# DAC.net
KiCad netlist of a schematic drawn in Altium Designer
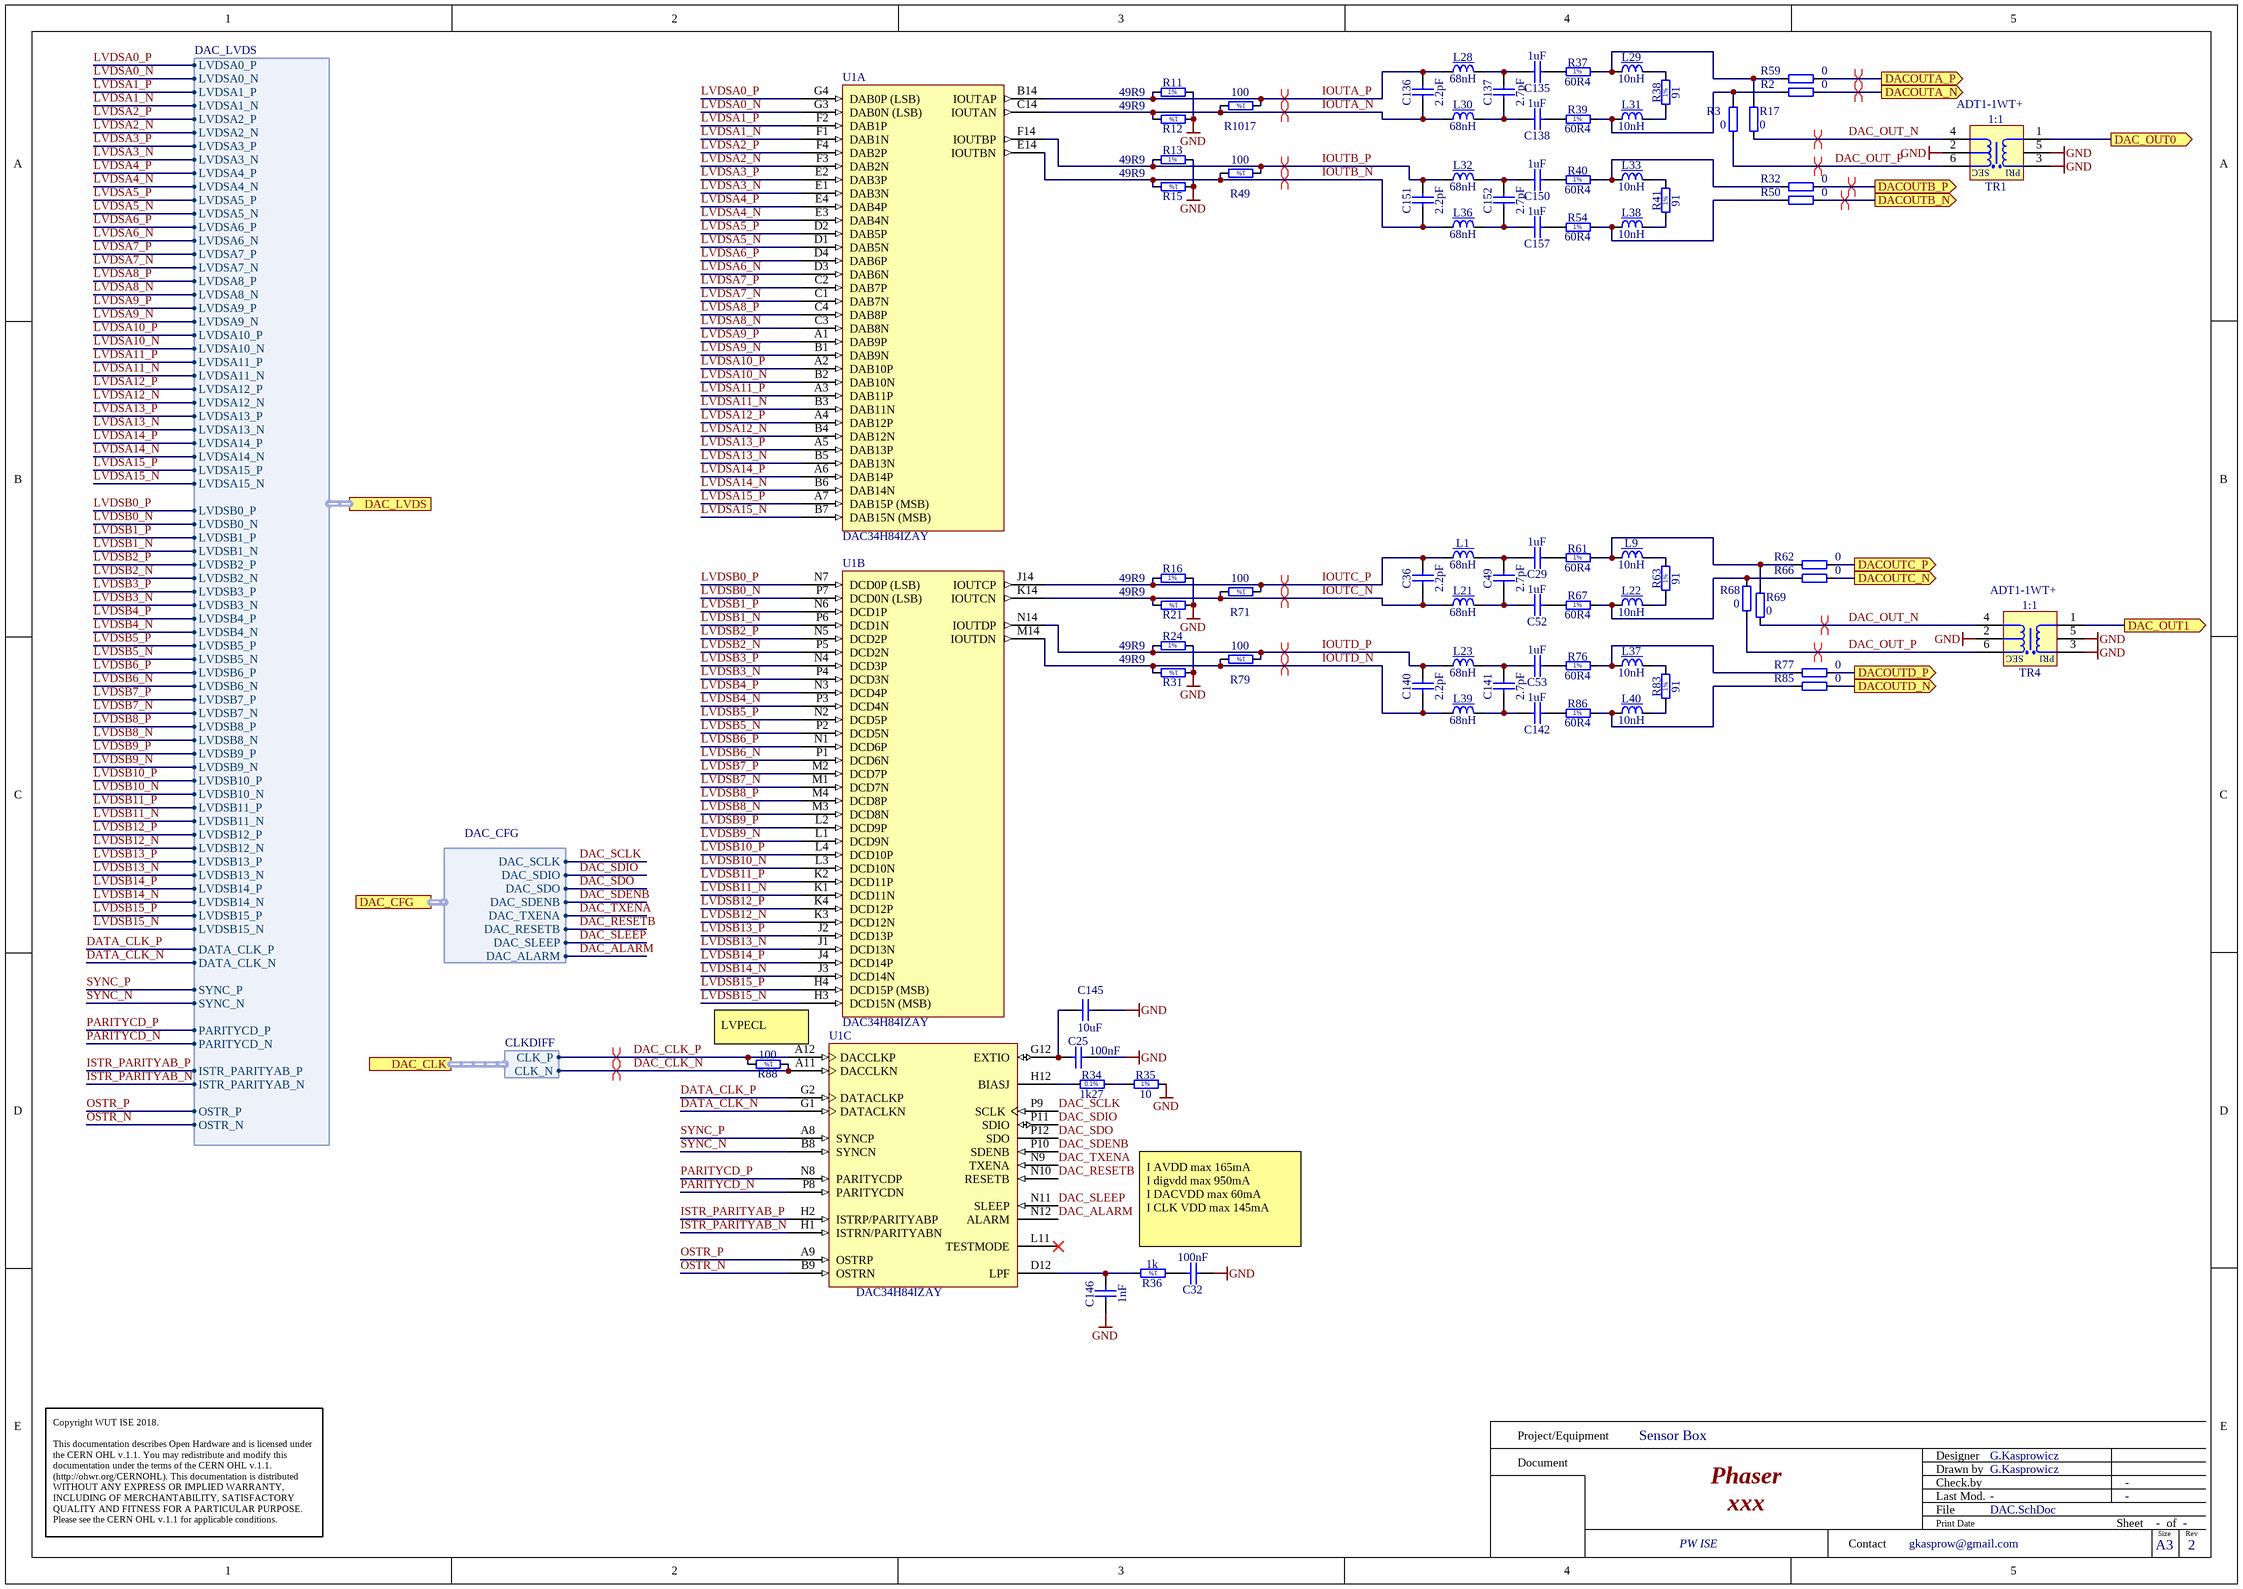
[diagram p0: DAC.SchDoc]

(export (version "E")
  (design (tool "Eeschema 10.0.6"))
  (components
    (comp (ref "C25")
      (value "100nF")
      (footprint "CAPC1005X55N")
      (description "Non-polarised capacitor")
      (fields (field (name "PART NUMBER") "CC0402_100NF_16V_10%_X5R") (field (name "VOLTAGE") "16V"))
      (libsource (lib "Capacitors") (part "Capacitor - non polarized"))
    )
    (comp (ref "C29")
      (value "1uF")
      (footprint "CAPC1005X55N")
      (description "Non-polarised capacitor")
      (fields (field (name "PART NUMBER") "CC0402_1UF_16V_10%_X5R") (field (name "VOLTAGE") "16V"))
      (libsource (lib "Capacitors") (part "Capacitor - non polarized"))
    )
    (comp (ref "C32")
      (value "100nF")
      (footprint "CAPC1608X90N")
      (description "Non-polarised capacitor")
      (fields (field (name "PART NUMBER") "CC0603_100NF_100V_10%_X7R") (field (name "VOLTAGE") "100V"))
      (libsource (lib "Capacitors") (part "Capacitor - non polarized"))
    )
    (comp (ref "C36")
      (value "2.2pF")
      (footprint "CAPC1608X87N")
      (description "Non-polarised capacitor")
      (fields (field (name "PART NUMBER") "CC0603_2.2PF_50V_0.25PF_NP0") (field (name "VOLTAGE") "50V"))
      (libsource (lib "Capacitors") (part "Capacitor - non polarized"))
    )
    (comp (ref "C49")
      (value "2.7pF")
      (footprint "CAPC1608X87N")
      (description "Non-polarised capacitor")
      (fields (field (name "PART NUMBER") "CC0603_2.7PF_50V_0.25PF_NP0") (field (name "VOLTAGE") "50V"))
      (libsource (lib "Capacitors") (part "Capacitor - non polarized"))
    )
    (comp (ref "C52")
      (value "1uF")
      (footprint "CAPC1005X55N")
      (description "Non-polarised capacitor")
      (fields (field (name "PART NUMBER") "CC0402_1UF_16V_10%_X5R") (field (name "VOLTAGE") "16V"))
      (libsource (lib "Capacitors") (part "Capacitor - non polarized"))
    )
    (comp (ref "C53")
      (value "1uF")
      (footprint "CAPC1005X55N")
      (description "Non-polarised capacitor")
      (fields (field (name "PART NUMBER") "CC0402_1UF_16V_10%_X5R") (field (name "VOLTAGE") "16V"))
      (libsource (lib "Capacitors") (part "Capacitor - non polarized"))
    )
    (comp (ref "C135")
      (value "1uF")
      (footprint "CAPC1005X55N")
      (description "Non-polarised capacitor")
      (fields (field (name "PART NUMBER") "CC0402_1UF_16V_10%_X5R") (field (name "VOLTAGE") "16V"))
      (libsource (lib "Capacitors") (part "Capacitor - non polarized"))
    )
    (comp (ref "C136")
      (value "2.2pF")
      (footprint "CAPC1608X87N")
      (description "Non-polarised capacitor")
      (fields (field (name "PART NUMBER") "CC0603_2.2PF_50V_0.25PF_NP0") (field (name "VOLTAGE") "50V"))
      (libsource (lib "Capacitors") (part "Capacitor - non polarized"))
    )
    (comp (ref "C137")
      (value "2.7pF")
      (footprint "CAPC1608X87N")
      (description "Non-polarised capacitor")
      (fields (field (name "PART NUMBER") "CC0603_2.7PF_50V_0.25PF_NP0") (field (name "VOLTAGE") "50V"))
      (libsource (lib "Capacitors") (part "Capacitor - non polarized"))
    )
    (comp (ref "C138")
      (value "1uF")
      (footprint "CAPC1005X55N")
      (description "Non-polarised capacitor")
      (fields (field (name "PART NUMBER") "CC0402_1UF_16V_10%_X5R") (field (name "VOLTAGE") "16V"))
      (libsource (lib "Capacitors") (part "Capacitor - non polarized"))
    )
    (comp (ref "C140")
      (value "2.2pF")
      (footprint "CAPC1608X87N")
      (description "Non-polarised capacitor")
      (fields (field (name "PART NUMBER") "CC0603_2.2PF_50V_0.25PF_NP0") (field (name "VOLTAGE") "50V"))
      (libsource (lib "Capacitors") (part "Capacitor - non polarized"))
    )
    (comp (ref "C141")
      (value "2.7pF")
      (footprint "CAPC1608X87N")
      (description "Non-polarised capacitor")
      (fields (field (name "PART NUMBER") "CC0603_2.7PF_50V_0.25PF_NP0") (field (name "VOLTAGE") "50V"))
      (libsource (lib "Capacitors") (part "Capacitor - non polarized"))
    )
    (comp (ref "C142")
      (value "1uF")
      (footprint "CAPC1005X55N")
      (description "Non-polarised capacitor")
      (fields (field (name "PART NUMBER") "CC0402_1UF_16V_10%_X5R") (field (name "VOLTAGE") "16V"))
      (libsource (lib "Capacitors") (part "Capacitor - non polarized"))
    )
    (comp (ref "C145")
      (value "10uF")
      (footprint "CAPC2012X95N")
      (description "Non-polarised capacitor")
      (fields (field (name "PART NUMBER") "CC0805_10UF_25V_10%_X5R") (field (name "VOLTAGE") "25V"))
      (libsource (lib "Capacitors") (part "Capacitor - non polarized"))
    )
    (comp (ref "C146")
      (value "1nF")
      (footprint "CAPC1608X90N")
      (description "Non-polarised capacitor")
      (fields (field (name "PART NUMBER") "CC0603_1NF_50V_1%_NP0") (field (name "VOLTAGE") "50V"))
      (libsource (lib "Capacitors") (part "Capacitor - non polarized"))
    )
    (comp (ref "C150")
      (value "1uF")
      (footprint "CAPC1005X55N")
      (description "Non-polarised capacitor")
      (fields (field (name "PART NUMBER") "CC0402_1UF_16V_10%_X5R") (field (name "VOLTAGE") "16V"))
      (libsource (lib "Capacitors") (part "Capacitor - non polarized"))
    )
    (comp (ref "C151")
      (value "2.2pF")
      (footprint "CAPC1608X87N")
      (description "Non-polarised capacitor")
      (fields (field (name "PART NUMBER") "CC0603_2.2PF_50V_0.25PF_NP0") (field (name "VOLTAGE") "50V"))
      (libsource (lib "Capacitors") (part "Capacitor - non polarized"))
    )
    (comp (ref "C152")
      (value "2.7pF")
      (footprint "CAPC1608X87N")
      (description "Non-polarised capacitor")
      (fields (field (name "PART NUMBER") "CC0603_2.7PF_50V_0.25PF_NP0") (field (name "VOLTAGE") "50V"))
      (libsource (lib "Capacitors") (part "Capacitor - non polarized"))
    )
    (comp (ref "C157")
      (value "1uF")
      (footprint "CAPC1005X55N")
      (description "Non-polarised capacitor")
      (fields (field (name "PART NUMBER") "CC0402_1UF_16V_10%_X5R") (field (name "VOLTAGE") "16V"))
      (libsource (lib "Capacitors") (part "Capacitor - non polarized"))
    )
    (comp (ref "L1")
      (value "68nH")
      (footprint "IND_COILCRAFT_0603HP")
      (description "Inductor With Core")
      (fields
        (field (name "PART NUMBER") "IND0603_68NH_2%_COILCRAFT_0603HP-68NXGLU")
        (field (name "POWER") "600mA")
      )
      (libsource (lib "Inductors & Transformers") (part "Inductor With Magnetic core"))
    )
    (comp (ref "L9")
      (value "10nH")
      (footprint "IND_COILCRAFT_0402DC")
      (description "Inductor With Core")
      (fields (field (name "PART NUMBER") "IND0402_10NH_2%_COILCRAFT_0402DC") (field (name "POWER") "1A"))
      (libsource (lib "Inductors_Transformers") (part "IND0402_10NH_2%_COILCRAFT_0402DC"))
    )
    (comp (ref "L21")
      (value "68nH")
      (footprint "IND_COILCRAFT_0603HP")
      (description "Inductor With Core")
      (fields
        (field (name "PART NUMBER") "IND0603_68NH_2%_COILCRAFT_0603HP-68NXGLU")
        (field (name "POWER") "600mA")
      )
      (libsource (lib "Inductors & Transformers") (part "Inductor With Magnetic core"))
    )
    (comp (ref "L22")
      (value "10nH")
      (footprint "IND_COILCRAFT_0402DC")
      (description "Inductor With Core")
      (fields (field (name "PART NUMBER") "IND0402_10NH_2%_COILCRAFT_0402DC") (field (name "POWER") "1A"))
      (libsource (lib "Inductors_Transformers") (part "IND0402_10NH_2%_COILCRAFT_0402DC"))
    )
    (comp (ref "L23")
      (value "68nH")
      (footprint "IND_COILCRAFT_0603HP")
      (description "Inductor With Core")
      (fields
        (field (name "PART NUMBER") "IND0603_68NH_2%_COILCRAFT_0603HP-68NXGLU")
        (field (name "POWER") "600mA")
      )
      (libsource (lib "Inductors & Transformers") (part "Inductor With Magnetic core"))
    )
    (comp (ref "L28")
      (value "68nH")
      (footprint "IND_COILCRAFT_0603HP")
      (description "Inductor With Core")
      (fields
        (field (name "PART NUMBER") "IND0603_68NH_2%_COILCRAFT_0603HP-68NXGLU")
        (field (name "POWER") "600mA")
      )
      (libsource (lib "Inductors & Transformers") (part "Inductor With Magnetic core"))
    )
    (comp (ref "L29")
      (value "10nH")
      (footprint "IND_COILCRAFT_0402DC")
      (description "Inductor With Core")
      (fields (field (name "PART NUMBER") "IND0402_10NH_2%_COILCRAFT_0402DC") (field (name "POWER") "1A"))
      (libsource (lib "Inductors_Transformers") (part "IND0402_10NH_2%_COILCRAFT_0402DC"))
    )
    (comp (ref "L30")
      (value "68nH")
      (footprint "IND_COILCRAFT_0603HP")
      (description "Inductor With Core")
      (fields
        (field (name "PART NUMBER") "IND0603_68NH_2%_COILCRAFT_0603HP-68NXGLU")
        (field (name "POWER") "600mA")
      )
      (libsource (lib "Inductors & Transformers") (part "Inductor With Magnetic core"))
    )
    (comp (ref "L31")
      (value "10nH")
      (footprint "IND_COILCRAFT_0402DC")
      (description "Inductor With Core")
      (fields (field (name "PART NUMBER") "IND0402_10NH_2%_COILCRAFT_0402DC") (field (name "POWER") "1A"))
      (libsource (lib "Inductors_Transformers") (part "IND0402_10NH_2%_COILCRAFT_0402DC"))
    )
    (comp (ref "L32")
      (value "68nH")
      (footprint "IND_COILCRAFT_0603HP")
      (description "Inductor With Core")
      (fields
        (field (name "PART NUMBER") "IND0603_68NH_2%_COILCRAFT_0603HP-68NXGLU")
        (field (name "POWER") "600mA")
      )
      (libsource (lib "Inductors & Transformers") (part "Inductor With Magnetic core"))
    )
    (comp (ref "L33")
      (value "10nH")
      (footprint "IND_COILCRAFT_0402DC")
      (description "Inductor With Core")
      (fields (field (name "PART NUMBER") "IND0402_10NH_2%_COILCRAFT_0402DC") (field (name "POWER") "1A"))
      (libsource (lib "Inductors_Transformers") (part "IND0402_10NH_2%_COILCRAFT_0402DC"))
    )
    (comp (ref "L36")
      (value "68nH")
      (footprint "IND_COILCRAFT_0603HP")
      (description "Inductor With Core")
      (fields
        (field (name "PART NUMBER") "IND0603_68NH_2%_COILCRAFT_0603HP-68NXGLU")
        (field (name "POWER") "600mA")
      )
      (libsource (lib "Inductors & Transformers") (part "Inductor With Magnetic core"))
    )
    (comp (ref "L37")
      (value "10nH")
      (footprint "IND_COILCRAFT_0402DC")
      (description "Inductor With Core")
      (fields (field (name "PART NUMBER") "IND0402_10NH_2%_COILCRAFT_0402DC") (field (name "POWER") "1A"))
      (libsource (lib "Inductors_Transformers") (part "IND0402_10NH_2%_COILCRAFT_0402DC"))
    )
    (comp (ref "L38")
      (value "10nH")
      (footprint "IND_COILCRAFT_0402DC")
      (description "Inductor With Core")
      (fields (field (name "PART NUMBER") "IND0402_10NH_2%_COILCRAFT_0402DC") (field (name "POWER") "1A"))
      (libsource (lib "Inductors_Transformers") (part "IND0402_10NH_2%_COILCRAFT_0402DC"))
    )
    (comp (ref "L39")
      (value "68nH")
      (footprint "IND_COILCRAFT_0603HP")
      (description "Inductor With Core")
      (fields
        (field (name "PART NUMBER") "IND0603_68NH_2%_COILCRAFT_0603HP-68NXGLU")
        (field (name "POWER") "600mA")
      )
      (libsource (lib "Inductors & Transformers") (part "Inductor With Magnetic core"))
    )
    (comp (ref "L40")
      (value "10nH")
      (footprint "IND_COILCRAFT_0402DC")
      (description "Inductor With Core")
      (fields (field (name "PART NUMBER") "IND0402_10NH_2%_COILCRAFT_0402DC") (field (name "POWER") "1A"))
      (libsource (lib "Inductors_Transformers") (part "IND0402_10NH_2%_COILCRAFT_0402DC"))
    )
    (comp (ref "R2")
      (value "0")
      (footprint "RESC1005X40N")
      (description "Resistor")
      (fields (field (name "PART NUMBER") "R0402_0R_JUMPER") (field (name "MANUFACTURER") "GENERIC"))
      (libsource (lib "Resistors") (part "Resistor"))
    )
    (comp (ref "R3")
      (value "0")
      (footprint "RESC1005X40N")
      (description "Resistor")
      (fields (field (name "PART NUMBER") "R0402_0R_JUMPER") (field (name "MANUFACTURER") "GENERIC"))
      (libsource (lib "Resistors") (part "Resistor"))
    )
    (comp (ref "R11")
      (value "49R9")
      (footprint "RESC1005X40N")
      (description "Resistor - 1%")
      (fields (field (name "PART NUMBER") "R0402_49R9_1%_0.0625W_100PPM") (field (name "POWER") "0.0625W"))
      (libsource (lib "Resistors") (part "Resistor - 1%"))
    )
    (comp (ref "R12")
      (value "49R9")
      (footprint "RESC1005X40N")
      (description "Resistor - 1%")
      (fields (field (name "PART NUMBER") "R0402_49R9_1%_0.0625W_100PPM") (field (name "POWER") "0.0625W"))
      (libsource (lib "Resistors") (part "Resistor - 1%"))
    )
    (comp (ref "R13")
      (value "49R9")
      (footprint "RESC1005X40N")
      (description "Resistor - 1%")
      (fields (field (name "PART NUMBER") "R0402_49R9_1%_0.0625W_100PPM") (field (name "POWER") "0.0625W"))
      (libsource (lib "Resistors") (part "Resistor - 1%"))
    )
    (comp (ref "R15")
      (value "49R9")
      (footprint "RESC1005X40N")
      (description "Resistor - 1%")
      (fields (field (name "PART NUMBER") "R0402_49R9_1%_0.0625W_100PPM") (field (name "POWER") "0.0625W"))
      (libsource (lib "Resistors") (part "Resistor - 1%"))
    )
    (comp (ref "R16")
      (value "49R9")
      (footprint "RESC1005X40N")
      (description "Resistor - 1%")
      (fields (field (name "PART NUMBER") "R0402_49R9_1%_0.0625W_100PPM") (field (name "POWER") "0.0625W"))
      (libsource (lib "Resistors") (part "Resistor - 1%"))
    )
    (comp (ref "R17")
      (value "0")
      (footprint "RESC1005X40N")
      (description "Resistor")
      (fields (field (name "PART NUMBER") "R0402_0R_JUMPER") (field (name "MANUFACTURER") "GENERIC"))
      (libsource (lib "Resistors") (part "Resistor"))
    )
    (comp (ref "R21")
      (value "49R9")
      (footprint "RESC1005X40N")
      (description "Resistor - 1%")
      (fields (field (name "PART NUMBER") "R0402_49R9_1%_0.0625W_100PPM") (field (name "POWER") "0.0625W"))
      (libsource (lib "Resistors") (part "Resistor - 1%"))
    )
    (comp (ref "R24")
      (value "49R9")
      (footprint "RESC1005X40N")
      (description "Resistor - 1%")
      (fields (field (name "PART NUMBER") "R0402_49R9_1%_0.0625W_100PPM") (field (name "POWER") "0.0625W"))
      (libsource (lib "Resistors") (part "Resistor - 1%"))
    )
    (comp (ref "R31")
      (value "49R9")
      (footprint "RESC1005X40N")
      (description "Resistor - 1%")
      (fields (field (name "PART NUMBER") "R0402_49R9_1%_0.0625W_100PPM") (field (name "POWER") "0.0625W"))
      (libsource (lib "Resistors") (part "Resistor - 1%"))
    )
    (comp (ref "R32")
      (value "0")
      (footprint "RESC1005X40N")
      (description "Resistor")
      (fields (field (name "PART NUMBER") "R0402_0R_JUMPER") (field (name "MANUFACTURER") "GENERIC"))
      (libsource (lib "Resistors") (part "Resistor"))
    )
    (comp (ref "R34")
      (value "1k27")
      (footprint "RESC1608X55N")
      (description "Resistor - 0.1%")
      (fields (field (name "PART NUMBER") "R0603_1K27_0.1%_0.063W_10PPM") (field (name "POWER") "0.063W"))
      (libsource (lib "Resistors") (part "Resistor - 0.1%"))
    )
    (comp (ref "R35")
      (value "10")
      (footprint "RESC1005X40N")
      (description "Resistor - 1%")
      (fields (field (name "PART NUMBER") "R0402_10R_1%_0.0625W_200PPM") (field (name "POWER") "0.0625W"))
      (libsource (lib "Resistors") (part "Resistor - 1%"))
    )
    (comp (ref "R36")
      (value "1k")
      (footprint "RESC1608X55N")
      (description "Resistor - 1%")
      (fields (field (name "PART NUMBER") "R0603_1K_1%_0.1W_100PPM") (field (name "POWER") "0.1W"))
      (libsource (lib "Resistors") (part "Resistor - 1%"))
    )
    (comp (ref "R37")
      (value "60R4")
      (footprint "RESC1005X40N")
      (description "Resistor - 1%")
      (fields (field (name "PART NUMBER") "R0402_60R4_1%_0.0625W_100PPM") (field (name "POWER") "0.0625W"))
      (libsource (lib "Passives_RC") (part "R0402_60R4_1%_0.0625W_100PPM"))
    )
    (comp (ref "R38")
      (value "91")
      (footprint "RESC1005X40N")
      (description "Resistor - 1%")
      (fields (field (name "PART NUMBER") "R0402_91R_1%_0.0625W_100PPM") (field (name "POWER") "0.0625W"))
      (libsource (lib "Resistors") (part "Resistor - 1%"))
    )
    (comp (ref "R39")
      (value "60R4")
      (footprint "RESC1005X40N")
      (description "Resistor - 1%")
      (fields (field (name "PART NUMBER") "R0402_60R4_1%_0.0625W_100PPM") (field (name "POWER") "0.0625W"))
      (libsource (lib "Passives_RC") (part "R0402_60R4_1%_0.0625W_100PPM"))
    )
    (comp (ref "R40")
      (value "60R4")
      (footprint "RESC1005X40N")
      (description "Resistor - 1%")
      (fields (field (name "PART NUMBER") "R0402_60R4_1%_0.0625W_100PPM") (field (name "POWER") "0.0625W"))
      (libsource (lib "Passives_RC") (part "R0402_60R4_1%_0.0625W_100PPM"))
    )
    (comp (ref "R41")
      (value "91")
      (footprint "RESC1005X40N")
      (description "Resistor - 1%")
      (fields (field (name "PART NUMBER") "R0402_91R_1%_0.0625W_100PPM") (field (name "POWER") "0.0625W"))
      (libsource (lib "Resistors") (part "Resistor - 1%"))
    )
    (comp (ref "R49")
      (value "100")
      (footprint "RESC0603X28N")
      (description "Resistor - 1%")
      (fields (field (name "PART NUMBER") "R0201_100R_1%_0.05W_200PPM") (field (name "POWER") "0.05W"))
      (libsource (lib "Resistors") (part "Resistor - 1%"))
    )
    (comp (ref "R50")
      (value "0")
      (footprint "RESC1005X40N")
      (description "Resistor")
      (fields (field (name "PART NUMBER") "R0402_0R_JUMPER") (field (name "MANUFACTURER") "GENERIC"))
      (libsource (lib "Resistors") (part "Resistor"))
    )
    (comp (ref "R54")
      (value "60R4")
      (footprint "RESC1005X40N")
      (description "Resistor - 1%")
      (fields (field (name "PART NUMBER") "R0402_60R4_1%_0.0625W_100PPM") (field (name "POWER") "0.0625W"))
      (libsource (lib "Passives_RC") (part "R0402_60R4_1%_0.0625W_100PPM"))
    )
    (comp (ref "R59")
      (value "0")
      (footprint "RESC1005X40N")
      (description "Resistor")
      (fields (field (name "PART NUMBER") "R0402_0R_JUMPER") (field (name "MANUFACTURER") "GENERIC"))
      (libsource (lib "Resistors") (part "Resistor"))
    )
    (comp (ref "R61")
      (value "60R4")
      (footprint "RESC1005X40N")
      (description "Resistor - 1%")
      (fields (field (name "PART NUMBER") "R0402_60R4_1%_0.0625W_100PPM") (field (name "POWER") "0.0625W"))
      (libsource (lib "Passives_RC") (part "R0402_60R4_1%_0.0625W_100PPM"))
    )
    (comp (ref "R62")
      (value "0")
      (footprint "RESC1005X40N")
      (description "Resistor")
      (fields (field (name "PART NUMBER") "R0402_0R_JUMPER") (field (name "MANUFACTURER") "GENERIC"))
      (libsource (lib "Resistors") (part "Resistor"))
    )
    (comp (ref "R63")
      (value "91")
      (footprint "RESC1005X40N")
      (description "Resistor - 1%")
      (fields (field (name "PART NUMBER") "R0402_91R_1%_0.0625W_100PPM") (field (name "POWER") "0.0625W"))
      (libsource (lib "Resistors") (part "Resistor - 1%"))
    )
    (comp (ref "R66")
      (value "0")
      (footprint "RESC1005X40N")
      (description "Resistor")
      (fields (field (name "PART NUMBER") "R0402_0R_JUMPER") (field (name "MANUFACTURER") "GENERIC"))
      (libsource (lib "Resistors") (part "Resistor"))
    )
    (comp (ref "R67")
      (value "60R4")
      (footprint "RESC1005X40N")
      (description "Resistor - 1%")
      (fields (field (name "PART NUMBER") "R0402_60R4_1%_0.0625W_100PPM") (field (name "POWER") "0.0625W"))
      (libsource (lib "Passives_RC") (part "R0402_60R4_1%_0.0625W_100PPM"))
    )
    (comp (ref "R68")
      (value "0")
      (footprint "RESC1005X40N")
      (description "Resistor")
      (fields (field (name "PART NUMBER") "R0402_0R_JUMPER") (field (name "MANUFACTURER") "GENERIC"))
      (libsource (lib "Resistors") (part "Resistor"))
    )
    (comp (ref "R69")
      (value "0")
      (footprint "RESC1005X40N")
      (description "Resistor")
      (fields (field (name "PART NUMBER") "R0402_0R_JUMPER") (field (name "MANUFACTURER") "GENERIC"))
      (libsource (lib "Resistors") (part "Resistor"))
    )
    (comp (ref "R71")
      (value "100")
      (footprint "RESC0603X28N")
      (description "Resistor - 1%")
      (fields (field (name "PART NUMBER") "R0201_100R_1%_0.05W_200PPM") (field (name "POWER") "0.05W"))
      (libsource (lib "Resistors") (part "Resistor - 1%"))
    )
    (comp (ref "R76")
      (value "60R4")
      (footprint "RESC1005X40N")
      (description "Resistor - 1%")
      (fields (field (name "PART NUMBER") "R0402_60R4_1%_0.0625W_100PPM") (field (name "POWER") "0.0625W"))
      (libsource (lib "Passives_RC") (part "R0402_60R4_1%_0.0625W_100PPM"))
    )
    (comp (ref "R77")
      (value "0")
      (footprint "RESC1005X40N")
      (description "Resistor")
      (fields (field (name "PART NUMBER") "R0402_0R_JUMPER") (field (name "MANUFACTURER") "GENERIC"))
      (libsource (lib "Resistors") (part "Resistor"))
    )
    (comp (ref "R79")
      (value "100")
      (footprint "RESC0603X28N")
      (description "Resistor - 1%")
      (fields (field (name "PART NUMBER") "R0201_100R_1%_0.05W_200PPM") (field (name "POWER") "0.05W"))
      (libsource (lib "Resistors") (part "Resistor - 1%"))
    )
    (comp (ref "R83")
      (value "91")
      (footprint "RESC1005X40N")
      (description "Resistor - 1%")
      (fields (field (name "PART NUMBER") "R0402_91R_1%_0.0625W_100PPM") (field (name "POWER") "0.0625W"))
      (libsource (lib "Resistors") (part "Resistor - 1%"))
    )
    (comp (ref "R85")
      (value "0")
      (footprint "RESC1005X40N")
      (description "Resistor")
      (fields (field (name "PART NUMBER") "R0402_0R_JUMPER") (field (name "MANUFACTURER") "GENERIC"))
      (libsource (lib "Resistors") (part "Resistor"))
    )
    (comp (ref "R86")
      (value "60R4")
      (footprint "RESC1005X40N")
      (description "Resistor - 1%")
      (fields (field (name "PART NUMBER") "R0402_60R4_1%_0.0625W_100PPM") (field (name "POWER") "0.0625W"))
      (libsource (lib "Passives_RC") (part "R0402_60R4_1%_0.0625W_100PPM"))
    )
    (comp (ref "R88")
      (value "100")
      (footprint "RESC0603X28N")
      (description "Resistor - 1%")
      (fields (field (name "PART NUMBER") "R0201_100R_1%_0.05W_200PPM") (field (name "POWER") "0.05W"))
      (libsource (lib "Resistors") (part "Resistor - 1%"))
    )
    (comp (ref "R1017")
      (value "100")
      (footprint "RESC0603X28N")
      (description "Resistor - 1%")
      (fields (field (name "PART NUMBER") "R0201_100R_1%_0.05W_200PPM") (field (name "POWER") "0.05W"))
      (libsource (lib "Resistors") (part "Resistor - 1%"))
    )
    (comp (ref "TR1")
      (value "1:1")
      (footprint "XFMR_MINI-CIRCUITS_CD542")
      (description "75 Ohm 0.4 To 800MHz RF Transformers")
      (fields
        (field (name "PART NUMBER") "XFMR_MINI-CIRCUITS_ADT1-1WT+")
        (field (name "MANUFACTURER") "MINI-CIRCUITS")
        (field (name "MANUFACTURER PART NUMBER") "ADT1-1WT+")
      )
      (libsource (lib "Inductors & Transformers") (part "XFMR_MINI-CIRCUITS_ADT1-1WT+"))
    )
    (comp (ref "TR4")
      (value "1:1")
      (footprint "XFMR_MINI-CIRCUITS_CD542")
      (description "75 Ohm 0.4 To 800MHz RF Transformers")
      (fields
        (field (name "PART NUMBER") "XFMR_MINI-CIRCUITS_ADT1-1WT+")
        (field (name "MANUFACTURER") "MINI-CIRCUITS")
        (field (name "MANUFACTURER PART NUMBER") "ADT1-1WT+")
      )
      (libsource (lib "Inductors & Transformers") (part "XFMR_MINI-CIRCUITS_ADT1-1WT+"))
    )
    (comp (ref "U1")
      (value "DAC34H84IZAY")
      (footprint "TI-ZAY196")
      (description "Quad-Channel, 16-Bit, 1.5 GSPS DAC, -40 to 85 degC, 196-pin BGA (ZAY196), Green (RoHS & no Sb/Br)")
      (fields (field (name "MANUFACTURER") "Texas Instruments"))
      (libsource (lib "Altium Content Vault") (part "TI-DAC34H_SH84-ZAY196"))
    )
  )
  (nets
    (net (code "4") (name "/DACOUTA_N") (class "Default")
      (node (ref "R2") (pin "1") (pinfunction "1_1") (pintype "passive"))
    )
    (net (code "5") (name "/DACOUTA_P") (class "Default")
      (node (ref "R59") (pin "1") (pinfunction "1_1") (pintype "passive"))
    )
    (net (code "6") (name "/DACOUTB_N") (class "Default")
      (node (ref "R50") (pin "1") (pinfunction "1_1") (pintype "passive"))
    )
    (net (code "7") (name "/DACOUTB_P") (class "Default")
      (node (ref "R32") (pin "1") (pinfunction "1_1") (pintype "passive"))
    )
    (net (code "8") (name "/DACOUTC_N") (class "Default")
      (node (ref "R66") (pin "1") (pinfunction "1_1") (pintype "passive"))
    )
    (net (code "9") (name "/DACOUTC_P") (class "Default")
      (node (ref "R62") (pin "1") (pinfunction "1_1") (pintype "passive"))
    )
    (net (code "10") (name "/DACOUTD_N") (class "Default")
      (node (ref "R85") (pin "1") (pinfunction "1_1") (pintype "passive"))
    )
    (net (code "11") (name "/DACOUTD_P") (class "Default")
      (node (ref "R77") (pin "1") (pinfunction "1_1") (pintype "passive"))
    )
    (net (code "12") (name "/DAC_ALARM") (class "Default")
      (node (ref "U1") (pin "N12") (pinfunction "ALARM_N12") (pintype "tri_state"))
    )
    (net (code "13") (name "/DAC_CLK_N") (class "Default")
      (node (ref "R88") (pin "1") (pinfunction "1_1") (pintype "passive"))
      (node (ref "U1") (pin "A11") (pinfunction "DACCLKN_A11") (pintype "input"))
    )
    (net (code "14") (name "/DAC_CLK_P") (class "Default")
      (node (ref "R88") (pin "2") (pinfunction "2_2") (pintype "passive"))
      (node (ref "U1") (pin "A12") (pinfunction "DACCLKP_A12") (pintype "input"))
    )
    (net (code "15") (name "/DAC_OUT0") (class "Default")
      (node (ref "TR1") (pin "1") (pinfunction "P_1") (pintype "passive"))
    )
    (net (code "16") (name "/DAC_OUT1") (class "Default")
      (node (ref "TR4") (pin "1") (pinfunction "P_1") (pintype "passive"))
    )
    (net (code "17") (name "/DAC_OUT_N") (class "Default")
      (node (ref "R17") (pin "1") (pinfunction "1_1") (pintype "passive"))
      (node (ref "R69") (pin "1") (pinfunction "1_1") (pintype "passive"))
      (node (ref "TR1") (pin "4") (pinfunction "S_4") (pintype "passive"))
      (node (ref "TR4") (pin "4") (pinfunction "S_4") (pintype "passive"))
    )
    (net (code "18") (name "/DAC_OUT_P") (class "Default")
      (node (ref "R3") (pin "1") (pinfunction "1_1") (pintype "passive"))
      (node (ref "R68") (pin "1") (pinfunction "1_1") (pintype "passive"))
      (node (ref "TR1") (pin "6") (pinfunction "SDOT_6") (pintype "passive"))
      (node (ref "TR4") (pin "6") (pinfunction "SDOT_6") (pintype "passive"))
    )
    (net (code "19") (name "/DAC_RESETB") (class "Default")
      (node (ref "U1") (pin "N10") (pinfunction "RESETB_N10") (pintype "input"))
    )
    (net (code "20") (name "/DAC_SCLK") (class "Default")
      (node (ref "U1") (pin "P9") (pinfunction "SCLK_P9") (pintype "input"))
    )
    (net (code "21") (name "/DAC_SDENB") (class "Default")
      (node (ref "U1") (pin "P10") (pinfunction "SDENB_P10") (pintype "input"))
    )
    (net (code "22") (name "/DAC_SDIO") (class "Default")
      (node (ref "U1") (pin "P11") (pinfunction "SDIO_P11") (pintype "bidirectional"))
    )
    (net (code "23") (name "/DAC_SDO") (class "Default")
      (node (ref "U1") (pin "P12") (pinfunction "SDO_P12") (pintype "tri_state"))
    )
    (net (code "24") (name "/DAC_SLEEP") (class "Default")
      (node (ref "U1") (pin "N11") (pinfunction "SLEEP_N11") (pintype "input"))
    )
    (net (code "25") (name "/DAC_TXENA") (class "Default")
      (node (ref "U1") (pin "N9") (pinfunction "TXENA_N9") (pintype "input"))
    )
    (net (code "26") (name "/DATA_CLK_N") (class "Default")
      (node (ref "U1") (pin "G1") (pinfunction "DATACLKN_G1") (pintype "input"))
    )
    (net (code "27") (name "/DATA_CLK_P") (class "Default")
      (node (ref "U1") (pin "G2") (pinfunction "DATACLKP_G2") (pintype "input"))
    )
    (net (code "28") (name "/IOUTA_N") (class "Default")
      (node (ref "C136") (pin "1") (pinfunction "1_1") (pintype "passive"))
      (node (ref "L30") (pin "1") (pinfunction "1_1") (pintype "passive"))
      (node (ref "R1017") (pin "2") (pinfunction "2_2") (pintype "passive"))
      (node (ref "R12") (pin "2") (pinfunction "2_2") (pintype "passive"))
      (node (ref "U1") (pin "C14") (pinfunction "IOUTAN_C14") (pintype "output"))
    )
    (net (code "29") (name "/IOUTA_P") (class "Default")
      (node (ref "C136") (pin "2") (pinfunction "2_2") (pintype "passive"))
      (node (ref "L28") (pin "1") (pinfunction "1_1") (pintype "passive"))
      (node (ref "R1017") (pin "1") (pinfunction "1_1") (pintype "passive"))
      (node (ref "R11") (pin "1") (pinfunction "1_1") (pintype "passive"))
      (node (ref "U1") (pin "B14") (pinfunction "IOUTAP_B14") (pintype "output"))
    )
    (net (code "30") (name "/IOUTB_N") (class "Default")
      (node (ref "C151") (pin "1") (pinfunction "1_1") (pintype "passive"))
      (node (ref "L36") (pin "1") (pinfunction "1_1") (pintype "passive"))
      (node (ref "R15") (pin "2") (pinfunction "2_2") (pintype "passive"))
      (node (ref "R49") (pin "2") (pinfunction "2_2") (pintype "passive"))
      (node (ref "U1") (pin "E14") (pinfunction "IOUTBN_E14") (pintype "output"))
    )
    (net (code "31") (name "/IOUTB_P") (class "Default")
      (node (ref "C151") (pin "2") (pinfunction "2_2") (pintype "passive"))
      (node (ref "L32") (pin "1") (pinfunction "1_1") (pintype "passive"))
      (node (ref "R13") (pin "1") (pinfunction "1_1") (pintype "passive"))
      (node (ref "R49") (pin "1") (pinfunction "1_1") (pintype "passive"))
      (node (ref "U1") (pin "F14") (pinfunction "IOUTBP_F14") (pintype "output"))
    )
    (net (code "32") (name "/IOUTC_N") (class "Default")
      (node (ref "C36") (pin "1") (pinfunction "1_1") (pintype "passive"))
      (node (ref "L21") (pin "1") (pinfunction "1_1") (pintype "passive"))
      (node (ref "R21") (pin "2") (pinfunction "2_2") (pintype "passive"))
      (node (ref "R71") (pin "2") (pinfunction "2_2") (pintype "passive"))
      (node (ref "U1") (pin "K14") (pinfunction "IOUTCN_K14") (pintype "output"))
    )
    (net (code "33") (name "/IOUTC_P") (class "Default")
      (node (ref "C36") (pin "2") (pinfunction "2_2") (pintype "passive"))
      (node (ref "L1") (pin "1") (pinfunction "1_1") (pintype "passive"))
      (node (ref "R16") (pin "1") (pinfunction "1_1") (pintype "passive"))
      (node (ref "R71") (pin "1") (pinfunction "1_1") (pintype "passive"))
      (node (ref "U1") (pin "J14") (pinfunction "IOUTCP_J14") (pintype "output"))
    )
    (net (code "34") (name "/IOUTD_N") (class "Default")
      (node (ref "C140") (pin "1") (pinfunction "1_1") (pintype "passive"))
      (node (ref "L39") (pin "1") (pinfunction "1_1") (pintype "passive"))
      (node (ref "R31") (pin "2") (pinfunction "2_2") (pintype "passive"))
      (node (ref "R79") (pin "2") (pinfunction "2_2") (pintype "passive"))
      (node (ref "U1") (pin "M14") (pinfunction "IOUTDN_M14") (pintype "output"))
    )
    (net (code "35") (name "/IOUTD_P") (class "Default")
      (node (ref "C140") (pin "2") (pinfunction "2_2") (pintype "passive"))
      (node (ref "L23") (pin "1") (pinfunction "1_1") (pintype "passive"))
      (node (ref "R24") (pin "1") (pinfunction "1_1") (pintype "passive"))
      (node (ref "R79") (pin "1") (pinfunction "1_1") (pintype "passive"))
      (node (ref "U1") (pin "N14") (pinfunction "IOUTDP_N14") (pintype "output"))
    )
    (net (code "36") (name "/ISTR_PARITYAB_N") (class "Default")
      (node (ref "U1") (pin "H1") (pinfunction "ISTRN/PARITYABN_H1") (pintype "input"))
    )
    (net (code "37") (name "/ISTR_PARITYAB_P") (class "Default")
      (node (ref "U1") (pin "H2") (pinfunction "ISTRP/PARITYABP_H2") (pintype "input"))
    )
    (net (code "38") (name "/LVDSA0_N") (class "Default")
      (node (ref "U1") (pin "G3") (pinfunction "DAB0N_(LSB)_G3") (pintype "input"))
    )
    (net (code "39") (name "/LVDSA0_P") (class "Default")
      (node (ref "U1") (pin "G4") (pinfunction "DAB0P_(LSB)_G4") (pintype "input"))
    )
    (net (code "40") (name "/LVDSA1_N") (class "Default")
      (node (ref "U1") (pin "F1") (pinfunction "DAB1N_F1") (pintype "input"))
    )
    (net (code "41") (name "/LVDSA1_P") (class "Default")
      (node (ref "U1") (pin "F2") (pinfunction "DAB1P_F2") (pintype "input"))
    )
    (net (code "42") (name "/LVDSA2_N") (class "Default")
      (node (ref "U1") (pin "F3") (pinfunction "DAB2N_F3") (pintype "input"))
    )
    (net (code "43") (name "/LVDSA2_P") (class "Default")
      (node (ref "U1") (pin "F4") (pinfunction "DAB2P_F4") (pintype "input"))
    )
    (net (code "44") (name "/LVDSA3_N") (class "Default")
      (node (ref "U1") (pin "E1") (pinfunction "DAB3N_E1") (pintype "input"))
    )
    (net (code "45") (name "/LVDSA3_P") (class "Default")
      (node (ref "U1") (pin "E2") (pinfunction "DAB3P_E2") (pintype "input"))
    )
    (net (code "46") (name "/LVDSA4_N") (class "Default")
      (node (ref "U1") (pin "E3") (pinfunction "DAB4N_E3") (pintype "input"))
    )
    (net (code "47") (name "/LVDSA4_P") (class "Default")
      (node (ref "U1") (pin "E4") (pinfunction "DAB4P_E4") (pintype "input"))
    )
    (net (code "48") (name "/LVDSA5_N") (class "Default")
      (node (ref "U1") (pin "D1") (pinfunction "DAB5N_D1") (pintype "input"))
    )
    (net (code "49") (name "/LVDSA5_P") (class "Default")
      (node (ref "U1") (pin "D2") (pinfunction "DAB5P_D2") (pintype "input"))
    )
    (net (code "50") (name "/LVDSA6_N") (class "Default")
      (node (ref "U1") (pin "D3") (pinfunction "DAB6N_D3") (pintype "input"))
    )
    (net (code "51") (name "/LVDSA6_P") (class "Default")
      (node (ref "U1") (pin "D4") (pinfunction "DAB6P_D4") (pintype "input"))
    )
    (net (code "52") (name "/LVDSA7_N") (class "Default")
      (node (ref "U1") (pin "C1") (pinfunction "DAB7N_C1") (pintype "input"))
    )
    (net (code "53") (name "/LVDSA7_P") (class "Default")
      (node (ref "U1") (pin "C2") (pinfunction "DAB7P_C2") (pintype "input"))
    )
    (net (code "54") (name "/LVDSA8_N") (class "Default")
      (node (ref "U1") (pin "C3") (pinfunction "DAB8N_C3") (pintype "input"))
    )
    (net (code "55") (name "/LVDSA8_P") (class "Default")
      (node (ref "U1") (pin "C4") (pinfunction "DAB8P_C4") (pintype "input"))
    )
    (net (code "56") (name "/LVDSA9_N") (class "Default")
      (node (ref "U1") (pin "B1") (pinfunction "DAB9N_B1") (pintype "input"))
    )
    (net (code "57") (name "/LVDSA9_P") (class "Default")
      (node (ref "U1") (pin "A1") (pinfunction "DAB9P_A1") (pintype "input"))
    )
    (net (code "58") (name "/LVDSA10_N") (class "Default")
      (node (ref "U1") (pin "B2") (pinfunction "DAB10N_B2") (pintype "input"))
    )
    (net (code "59") (name "/LVDSA10_P") (class "Default")
      (node (ref "U1") (pin "A2") (pinfunction "DAB10P_A2") (pintype "input"))
    )
    (net (code "60") (name "/LVDSA11_N") (class "Default")
      (node (ref "U1") (pin "B3") (pinfunction "DAB11N_B3") (pintype "input"))
    )
    (net (code "61") (name "/LVDSA11_P") (class "Default")
      (node (ref "U1") (pin "A3") (pinfunction "DAB11P_A3") (pintype "input"))
    )
    (net (code "62") (name "/LVDSA12_N") (class "Default")
      (node (ref "U1") (pin "B4") (pinfunction "DAB12N_B4") (pintype "input"))
    )
    (net (code "63") (name "/LVDSA12_P") (class "Default")
      (node (ref "U1") (pin "A4") (pinfunction "DAB12P_A4") (pintype "input"))
    )
    (net (code "64") (name "/LVDSA13_N") (class "Default")
      (node (ref "U1") (pin "B5") (pinfunction "DAB13N_B5") (pintype "input"))
    )
    (net (code "65") (name "/LVDSA13_P") (class "Default")
      (node (ref "U1") (pin "A5") (pinfunction "DAB13P_A5") (pintype "input"))
    )
    (net (code "66") (name "/LVDSA14_N") (class "Default")
      (node (ref "U1") (pin "B6") (pinfunction "DAB14N_B6") (pintype "input"))
    )
    (net (code "67") (name "/LVDSA14_P") (class "Default")
      (node (ref "U1") (pin "A6") (pinfunction "DAB14P_A6") (pintype "input"))
    )
    (net (code "68") (name "/LVDSA15_N") (class "Default")
      (node (ref "U1") (pin "B7") (pinfunction "DAB15N_(MSB)_B7") (pintype "input"))
    )
    (net (code "69") (name "/LVDSA15_P") (class "Default")
      (node (ref "U1") (pin "A7") (pinfunction "DAB15P_(MSB)_A7") (pintype "input"))
    )
    (net (code "70") (name "/LVDSB0_N") (class "Default")
      (node (ref "U1") (pin "P7") (pinfunction "DCD0N_(LSB)_P7") (pintype "input"))
    )
    (net (code "71") (name "/LVDSB0_P") (class "Default")
      (node (ref "U1") (pin "N7") (pinfunction "DCD0P_(LSB)_N7") (pintype "input"))
    )
    (net (code "72") (name "/LVDSB1_N") (class "Default")
      (node (ref "U1") (pin "P6") (pinfunction "DCD1N_P6") (pintype "input"))
    )
    (net (code "73") (name "/LVDSB1_P") (class "Default")
      (node (ref "U1") (pin "N6") (pinfunction "DCD1P_N6") (pintype "input"))
    )
    (net (code "74") (name "/LVDSB2_N") (class "Default")
      (node (ref "U1") (pin "P5") (pinfunction "DCD2N_P5") (pintype "input"))
    )
    (net (code "75") (name "/LVDSB2_P") (class "Default")
      (node (ref "U1") (pin "N5") (pinfunction "DCD2P_N5") (pintype "input"))
    )
    (net (code "76") (name "/LVDSB3_N") (class "Default")
      (node (ref "U1") (pin "P4") (pinfunction "DCD3N_P4") (pintype "input"))
    )
    (net (code "77") (name "/LVDSB3_P") (class "Default")
      (node (ref "U1") (pin "N4") (pinfunction "DCD3P_N4") (pintype "input"))
    )
    (net (code "78") (name "/LVDSB4_N") (class "Default")
      (node (ref "U1") (pin "P3") (pinfunction "DCD4N_P3") (pintype "input"))
    )
    (net (code "79") (name "/LVDSB4_P") (class "Default")
      (node (ref "U1") (pin "N3") (pinfunction "DCD4P_N3") (pintype "input"))
    )
    (net (code "80") (name "/LVDSB5_N") (class "Default")
      (node (ref "U1") (pin "P2") (pinfunction "DCD5N_P2") (pintype "input"))
    )
    (net (code "81") (name "/LVDSB5_P") (class "Default")
      (node (ref "U1") (pin "N2") (pinfunction "DCD5P_N2") (pintype "input"))
    )
    (net (code "82") (name "/LVDSB6_N") (class "Default")
      (node (ref "U1") (pin "P1") (pinfunction "DCD6N_P1") (pintype "input"))
    )
    (net (code "83") (name "/LVDSB6_P") (class "Default")
      (node (ref "U1") (pin "N1") (pinfunction "DCD6P_N1") (pintype "input"))
    )
    (net (code "84") (name "/LVDSB7_N") (class "Default")
      (node (ref "U1") (pin "M1") (pinfunction "DCD7N_M1") (pintype "input"))
    )
    (net (code "85") (name "/LVDSB7_P") (class "Default")
      (node (ref "U1") (pin "M2") (pinfunction "DCD7P_M2") (pintype "input"))
    )
    (net (code "86") (name "/LVDSB8_N") (class "Default")
      (node (ref "U1") (pin "M3") (pinfunction "DCD8N_M3") (pintype "input"))
    )
    (net (code "87") (name "/LVDSB8_P") (class "Default")
      (node (ref "U1") (pin "M4") (pinfunction "DCD8P_M4") (pintype "input"))
    )
    (net (code "88") (name "/LVDSB9_N") (class "Default")
      (node (ref "U1") (pin "L1") (pinfunction "DCD9N_L1") (pintype "input"))
    )
    (net (code "89") (name "/LVDSB9_P") (class "Default")
      (node (ref "U1") (pin "L2") (pinfunction "DCD9P_L2") (pintype "input"))
    )
    (net (code "90") (name "/LVDSB10_N") (class "Default")
      (node (ref "U1") (pin "L3") (pinfunction "DCD10N_L3") (pintype "input"))
    )
    (net (code "91") (name "/LVDSB10_P") (class "Default")
      (node (ref "U1") (pin "L4") (pinfunction "DCD10P_L4") (pintype "input"))
    )
    (net (code "92") (name "/LVDSB11_N") (class "Default")
      (node (ref "U1") (pin "K1") (pinfunction "DCD11N_K1") (pintype "input"))
    )
    (net (code "93") (name "/LVDSB11_P") (class "Default")
      (node (ref "U1") (pin "K2") (pinfunction "DCD11P_K2") (pintype "input"))
    )
    (net (code "94") (name "/LVDSB12_N") (class "Default")
      (node (ref "U1") (pin "K3") (pinfunction "DCD12N_K3") (pintype "input"))
    )
    (net (code "95") (name "/LVDSB12_P") (class "Default")
      (node (ref "U1") (pin "K4") (pinfunction "DCD12P_K4") (pintype "input"))
    )
    (net (code "96") (name "/LVDSB13_N") (class "Default")
      (node (ref "U1") (pin "J1") (pinfunction "DCD13N_J1") (pintype "input"))
    )
    (net (code "97") (name "/LVDSB13_P") (class "Default")
      (node (ref "U1") (pin "J2") (pinfunction "DCD13P_J2") (pintype "input"))
    )
    (net (code "98") (name "/LVDSB14_N") (class "Default")
      (node (ref "U1") (pin "J3") (pinfunction "DCD14N_J3") (pintype "input"))
    )
    (net (code "99") (name "/LVDSB14_P") (class "Default")
      (node (ref "U1") (pin "J4") (pinfunction "DCD14P_J4") (pintype "input"))
    )
    (net (code "100") (name "/LVDSB15_N") (class "Default")
      (node (ref "U1") (pin "H3") (pinfunction "DCD15N_(MSB)_H3") (pintype "input"))
    )
    (net (code "101") (name "/LVDSB15_P") (class "Default")
      (node (ref "U1") (pin "H4") (pinfunction "DCD15P_(MSB)_H4") (pintype "input"))
    )
    (net (code "102") (name "/OSTR_N") (class "Default")
      (node (ref "U1") (pin "B9") (pinfunction "OSTRN_B9") (pintype "input"))
    )
    (net (code "103") (name "/OSTR_P") (class "Default")
      (node (ref "U1") (pin "A9") (pinfunction "OSTRP_A9") (pintype "input"))
    )
    (net (code "104") (name "/PARITYCD_N") (class "Default")
      (node (ref "U1") (pin "P8") (pinfunction "PARITYCDN_P8") (pintype "input"))
    )
    (net (code "105") (name "/PARITYCD_P") (class "Default")
      (node (ref "U1") (pin "N8") (pinfunction "PARITYCDP_N8") (pintype "input"))
    )
    (net (code "106") (name "/SYNC_N") (class "Default")
      (node (ref "U1") (pin "B8") (pinfunction "SYNCN_B8") (pintype "input"))
    )
    (net (code "107") (name "/SYNC_P") (class "Default")
      (node (ref "U1") (pin "A8") (pinfunction "SYNCP_A8") (pintype "input"))
    )
    (net (code "111") (name "GND") (class "Default")
      (node (ref "C145") (pin "1") (pinfunction "1_1") (pintype "passive"))
      (node (ref "C146") (pin "1") (pinfunction "1_1") (pintype "passive"))
      (node (ref "C25") (pin "2") (pinfunction "2_2") (pintype "passive"))
      (node (ref "C32") (pin "1") (pinfunction "1_1") (pintype "passive"))
      (node (ref "R11") (pin "2") (pinfunction "2_2") (pintype "passive"))
      (node (ref "R12") (pin "1") (pinfunction "1_1") (pintype "passive"))
      (node (ref "R13") (pin "2") (pinfunction "2_2") (pintype "passive"))
      (node (ref "R15") (pin "1") (pinfunction "1_1") (pintype "passive"))
      (node (ref "R16") (pin "2") (pinfunction "2_2") (pintype "passive"))
      (node (ref "R21") (pin "1") (pinfunction "1_1") (pintype "passive"))
      (node (ref "R24") (pin "2") (pinfunction "2_2") (pintype "passive"))
      (node (ref "R31") (pin "1") (pinfunction "1_1") (pintype "passive"))
      (node (ref "R35") (pin "2") (pinfunction "2_2") (pintype "passive"))
      (node (ref "TR1") (pin "2") (pinfunction "SCT_2") (pintype "passive"))
      (node (ref "TR1") (pin "3") (pinfunction "PDOT_3") (pintype "passive"))
      (node (ref "TR1") (pin "5") (pinfunction "NC_5") (pintype "passive"))
      (node (ref "TR4") (pin "2") (pinfunction "SCT_2") (pintype "passive"))
      (node (ref "TR4") (pin "3") (pinfunction "PDOT_3") (pintype "passive"))
      (node (ref "TR4") (pin "5") (pinfunction "NC_5") (pintype "passive"))
    )
    (net (code "112") (name "Net-(C29-Pad1)") (class "Default")
      (node (ref "C29") (pin "1") (pinfunction "1_1") (pintype "passive"))
      (node (ref "R61") (pin "1") (pinfunction "1_1") (pintype "passive"))
    )
    (net (code "113") (name "Net-(C29-Pad2)") (class "Default")
      (node (ref "C29") (pin "2") (pinfunction "2_2") (pintype "passive"))
      (node (ref "C49") (pin "2") (pinfunction "2_2") (pintype "passive"))
      (node (ref "L1") (pin "2") (pinfunction "2_2") (pintype "passive"))
    )
    (net (code "114") (name "Net-(C32-Pad2)") (class "Default")
      (node (ref "C32") (pin "2") (pinfunction "2_2") (pintype "passive"))
      (node (ref "R36") (pin "1") (pinfunction "1_1") (pintype "passive"))
    )
    (net (code "115") (name "Net-(C49-Pad1)") (class "Default")
      (node (ref "C49") (pin "1") (pinfunction "1_1") (pintype "passive"))
      (node (ref "C52") (pin "2") (pinfunction "2_2") (pintype "passive"))
      (node (ref "L21") (pin "2") (pinfunction "2_2") (pintype "passive"))
    )
    (net (code "116") (name "Net-(C52-Pad1)") (class "Default")
      (node (ref "C52") (pin "1") (pinfunction "1_1") (pintype "passive"))
      (node (ref "R67") (pin "1") (pinfunction "1_1") (pintype "passive"))
    )
    (net (code "117") (name "Net-(C53-Pad1)") (class "Default")
      (node (ref "C53") (pin "1") (pinfunction "1_1") (pintype "passive"))
      (node (ref "R76") (pin "1") (pinfunction "1_1") (pintype "passive"))
    )
    (net (code "118") (name "Net-(C135-Pad1)") (class "Default")
      (node (ref "C135") (pin "1") (pinfunction "1_1") (pintype "passive"))
      (node (ref "R37") (pin "1") (pinfunction "1_1") (pintype "passive"))
    )
    (net (code "119") (name "Net-(C135-Pad2)") (class "Default")
      (node (ref "C135") (pin "2") (pinfunction "2_2") (pintype "passive"))
      (node (ref "C137") (pin "2") (pinfunction "2_2") (pintype "passive"))
      (node (ref "L28") (pin "2") (pinfunction "2_2") (pintype "passive"))
    )
    (net (code "120") (name "Net-(C137-Pad1)") (class "Default")
      (node (ref "C137") (pin "1") (pinfunction "1_1") (pintype "passive"))
      (node (ref "C138") (pin "2") (pinfunction "2_2") (pintype "passive"))
      (node (ref "L30") (pin "2") (pinfunction "2_2") (pintype "passive"))
    )
    (net (code "121") (name "Net-(C138-Pad1)") (class "Default")
      (node (ref "C138") (pin "1") (pinfunction "1_1") (pintype "passive"))
      (node (ref "R39") (pin "1") (pinfunction "1_1") (pintype "passive"))
    )
    (net (code "122") (name "Net-(C141-Pad1)") (class "Default")
      (node (ref "C141") (pin "1") (pinfunction "1_1") (pintype "passive"))
      (node (ref "C142") (pin "2") (pinfunction "2_2") (pintype "passive"))
      (node (ref "L39") (pin "2") (pinfunction "2_2") (pintype "passive"))
    )
    (net (code "123") (name "Net-(C141-Pad2)") (class "Default")
      (node (ref "C141") (pin "2") (pinfunction "2_2") (pintype "passive"))
      (node (ref "C53") (pin "2") (pinfunction "2_2") (pintype "passive"))
      (node (ref "L23") (pin "2") (pinfunction "2_2") (pintype "passive"))
    )
    (net (code "124") (name "Net-(C142-Pad1)") (class "Default")
      (node (ref "C142") (pin "1") (pinfunction "1_1") (pintype "passive"))
      (node (ref "R86") (pin "1") (pinfunction "1_1") (pintype "passive"))
    )
    (net (code "125") (name "Net-(C150-Pad1)") (class "Default")
      (node (ref "C150") (pin "1") (pinfunction "1_1") (pintype "passive"))
      (node (ref "R40") (pin "1") (pinfunction "1_1") (pintype "passive"))
    )
    (net (code "126") (name "Net-(C150-Pad2)") (class "Default")
      (node (ref "C150") (pin "2") (pinfunction "2_2") (pintype "passive"))
      (node (ref "C152") (pin "2") (pinfunction "2_2") (pintype "passive"))
      (node (ref "L32") (pin "2") (pinfunction "2_2") (pintype "passive"))
    )
    (net (code "127") (name "Net-(C152-Pad1)") (class "Default")
      (node (ref "C152") (pin "1") (pinfunction "1_1") (pintype "passive"))
      (node (ref "C157") (pin "2") (pinfunction "2_2") (pintype "passive"))
      (node (ref "L36") (pin "2") (pinfunction "2_2") (pintype "passive"))
    )
    (net (code "128") (name "Net-(C157-Pad1)") (class "Default")
      (node (ref "C157") (pin "1") (pinfunction "1_1") (pintype "passive"))
      (node (ref "R54") (pin "1") (pinfunction "1_1") (pintype "passive"))
    )
    (net (code "129") (name "Net-(L9-Pad1)") (class "Default")
      (node (ref "L9") (pin "1") (pinfunction "1_1") (pintype "passive"))
      (node (ref "R61") (pin "2") (pinfunction "2_2") (pintype "passive"))
      (node (ref "R62") (pin "2") (pinfunction "2_2") (pintype "passive"))
      (node (ref "R69") (pin "2") (pinfunction "2_2") (pintype "passive"))
    )
    (net (code "130") (name "Net-(L9-Pad2)") (class "Default")
      (node (ref "L9") (pin "2") (pinfunction "2_2") (pintype "passive"))
      (node (ref "R63") (pin "2") (pinfunction "2_2") (pintype "passive"))
    )
    (net (code "131") (name "Net-(L22-Pad1)") (class "Default")
      (node (ref "L22") (pin "1") (pinfunction "1_1") (pintype "passive"))
      (node (ref "R66") (pin "2") (pinfunction "2_2") (pintype "passive"))
      (node (ref "R67") (pin "2") (pinfunction "2_2") (pintype "passive"))
      (node (ref "R68") (pin "2") (pinfunction "2_2") (pintype "passive"))
    )
    (net (code "132") (name "Net-(L22-Pad2)") (class "Default")
      (node (ref "L22") (pin "2") (pinfunction "2_2") (pintype "passive"))
      (node (ref "R63") (pin "1") (pinfunction "1_1") (pintype "passive"))
    )
    (net (code "133") (name "Net-(L29-Pad1)") (class "Default")
      (node (ref "L29") (pin "1") (pinfunction "1_1") (pintype "passive"))
      (node (ref "R17") (pin "2") (pinfunction "2_2") (pintype "passive"))
      (node (ref "R37") (pin "2") (pinfunction "2_2") (pintype "passive"))
      (node (ref "R59") (pin "2") (pinfunction "2_2") (pintype "passive"))
    )
    (net (code "134") (name "Net-(L29-Pad2)") (class "Default")
      (node (ref "L29") (pin "2") (pinfunction "2_2") (pintype "passive"))
      (node (ref "R38") (pin "2") (pinfunction "2_2") (pintype "passive"))
    )
    (net (code "135") (name "Net-(L31-Pad1)") (class "Default")
      (node (ref "L31") (pin "1") (pinfunction "1_1") (pintype "passive"))
      (node (ref "R2") (pin "2") (pinfunction "2_2") (pintype "passive"))
      (node (ref "R3") (pin "2") (pinfunction "2_2") (pintype "passive"))
      (node (ref "R39") (pin "2") (pinfunction "2_2") (pintype "passive"))
    )
    (net (code "136") (name "Net-(L31-Pad2)") (class "Default")
      (node (ref "L31") (pin "2") (pinfunction "2_2") (pintype "passive"))
      (node (ref "R38") (pin "1") (pinfunction "1_1") (pintype "passive"))
    )
    (net (code "137") (name "Net-(L33-Pad1)") (class "Default")
      (node (ref "L33") (pin "1") (pinfunction "1_1") (pintype "passive"))
      (node (ref "R32") (pin "2") (pinfunction "2_2") (pintype "passive"))
      (node (ref "R40") (pin "2") (pinfunction "2_2") (pintype "passive"))
    )
    (net (code "138") (name "Net-(L33-Pad2)") (class "Default")
      (node (ref "L33") (pin "2") (pinfunction "2_2") (pintype "passive"))
      (node (ref "R41") (pin "2") (pinfunction "2_2") (pintype "passive"))
    )
    (net (code "139") (name "Net-(L37-Pad1)") (class "Default")
      (node (ref "L37") (pin "1") (pinfunction "1_1") (pintype "passive"))
      (node (ref "R76") (pin "2") (pinfunction "2_2") (pintype "passive"))
      (node (ref "R77") (pin "2") (pinfunction "2_2") (pintype "passive"))
    )
    (net (code "140") (name "Net-(L37-Pad2)") (class "Default")
      (node (ref "L37") (pin "2") (pinfunction "2_2") (pintype "passive"))
      (node (ref "R83") (pin "2") (pinfunction "2_2") (pintype "passive"))
    )
    (net (code "141") (name "Net-(L38-Pad1)") (class "Default")
      (node (ref "L38") (pin "1") (pinfunction "1_1") (pintype "passive"))
      (node (ref "R50") (pin "2") (pinfunction "2_2") (pintype "passive"))
      (node (ref "R54") (pin "2") (pinfunction "2_2") (pintype "passive"))
    )
    (net (code "142") (name "Net-(L38-Pad2)") (class "Default")
      (node (ref "L38") (pin "2") (pinfunction "2_2") (pintype "passive"))
      (node (ref "R41") (pin "1") (pinfunction "1_1") (pintype "passive"))
    )
    (net (code "143") (name "Net-(L40-Pad1)") (class "Default")
      (node (ref "L40") (pin "1") (pinfunction "1_1") (pintype "passive"))
      (node (ref "R85") (pin "2") (pinfunction "2_2") (pintype "passive"))
      (node (ref "R86") (pin "2") (pinfunction "2_2") (pintype "passive"))
    )
    (net (code "144") (name "Net-(L40-Pad2)") (class "Default")
      (node (ref "L40") (pin "2") (pinfunction "2_2") (pintype "passive"))
      (node (ref "R83") (pin "1") (pinfunction "1_1") (pintype "passive"))
    )
    (net (code "145") (name "Net-(R34-Pad2)") (class "Default")
      (node (ref "R34") (pin "2") (pinfunction "2_2") (pintype "passive"))
      (node (ref "R35") (pin "1") (pinfunction "1_1") (pintype "passive"))
    )
    (net (code "146") (name "Net-(U1C-BIASJ)") (class "Default")
      (node (ref "R34") (pin "1") (pinfunction "1_1") (pintype "passive"))
      (node (ref "U1") (pin "H12") (pinfunction "BIASJ_H12") (pintype "passive"))
    )
    (net (code "147") (name "Net-(U1C-EXTIO)") (class "Default")
      (node (ref "C145") (pin "2") (pinfunction "2_2") (pintype "passive"))
      (node (ref "C25") (pin "1") (pinfunction "1_1") (pintype "passive"))
      (node (ref "U1") (pin "G12") (pinfunction "EXTIO_G12") (pintype "bidirectional"))
    )
    (net (code "148") (name "Net-(U1C-LPF)") (class "Default")
      (node (ref "C146") (pin "2") (pinfunction "2_2") (pintype "passive"))
      (node (ref "R36") (pin "2") (pinfunction "2_2") (pintype "passive"))
      (node (ref "U1") (pin "D12") (pinfunction "LPF_D12") (pintype "passive"))
    )
    (net (code "149") (name "unconnected-(U1C-TESTMODE-PadL11)") (class "Default")
      (node (ref "U1") (pin "L11") (pinfunction "TESTMODE_L11") (pintype "passive+no_connect"))
    )
  )
)
